# LineCliffSensors.net
KiCad netlist of a schematic drawn in Altium Designer
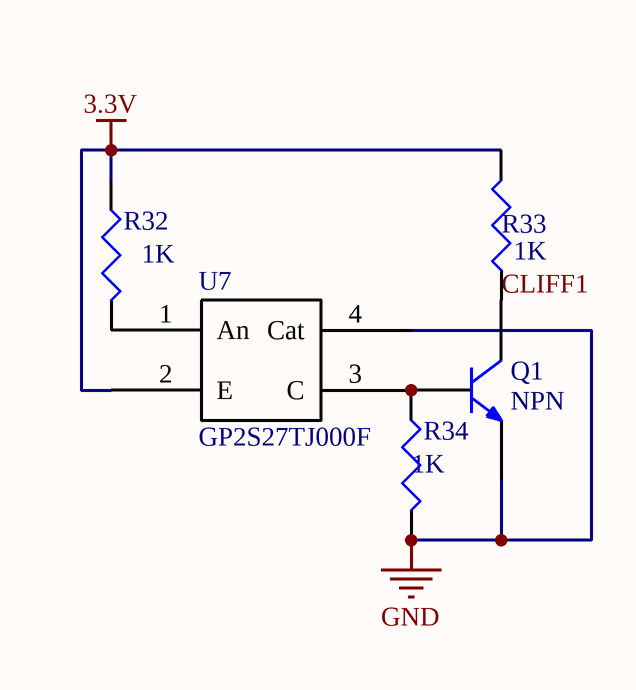
[diagram p0: LineCliffSensors.SchDoc]

(export (version "E")
  (design (tool "Eeschema 10.0.6"))
  (components
    (comp (ref "Q1") (value "NPN") (footprint "SOT-23") (libsource (lib "mrone") (part "NPN")))
    (comp (ref "R32")
      (value "1K")
      (footprint "RESC1608L")
      (description "Resistor")
      (fields (field (name "Comment") "Res3") (field (name "PUBLISHER") "Altium Limited"))
      (libsource (lib "Miscellaneous Devices") (part "Res3"))
    )
    (comp (ref "R33")
      (value "1K")
      (footprint "RESC1608L")
      (description "Resistor")
      (fields (field (name "Comment") "Res3") (field (name "PUBLISHER") "Altium Limited"))
      (libsource (lib "Miscellaneous Devices") (part "Res3"))
    )
    (comp (ref "R34")
      (value "1K")
      (footprint "RESC1608L")
      (description "Resistor")
      (fields (field (name "Comment") "Res3") (field (name "PUBLISHER") "Altium Limited"))
      (libsource (lib "Miscellaneous Devices") (part "Res3"))
    )
    (comp (ref "U7")
      (value "GP2S27TJ000F")
      (footprint "GP2S27J0000F")
      (libsource (lib "mrone") (part "GP2S27TJ000F"))
    )
  )
  (nets
    (net (code "1") (name "/CLIFF1") (class "Default")
      (node (ref "Q1") (pin "3") (pinfunction "C_3") (pintype "passive"))
      (node (ref "R33") (pin "1") (pinfunction "1_1") (pintype "passive"))
    )
    (net (code "2") (name "3.3V") (class "Default")
      (node (ref "R32") (pin "1") (pinfunction "1_1") (pintype "passive"))
      (node (ref "R33") (pin "2") (pinfunction "2_2") (pintype "passive"))
      (node (ref "U7") (pin "2") (pinfunction "E_2") (pintype "passive"))
    )
    (net (code "3") (name "GND") (class "Default")
      (node (ref "Q1") (pin "2") (pinfunction "E_2") (pintype "passive"))
      (node (ref "R34") (pin "2") (pinfunction "2_2") (pintype "passive"))
      (node (ref "U7") (pin "4") (pinfunction "Cat_4") (pintype "passive"))
    )
    (net (code "4") (name "Net-(Q1-B)") (class "Default")
      (node (ref "Q1") (pin "1") (pinfunction "B_1") (pintype "passive"))
      (node (ref "R34") (pin "1") (pinfunction "1_1") (pintype "passive"))
      (node (ref "U7") (pin "3") (pinfunction "C_3") (pintype "passive"))
    )
    (net (code "5") (name "Net-(U7-An)") (class "Default")
      (node (ref "R32") (pin "2") (pinfunction "2_2") (pintype "passive"))
      (node (ref "U7") (pin "1") (pinfunction "An_1") (pintype "passive"))
    )
  )
)
